# contra1579.net
KiCad netlist of a schematic drawn in EAGLE
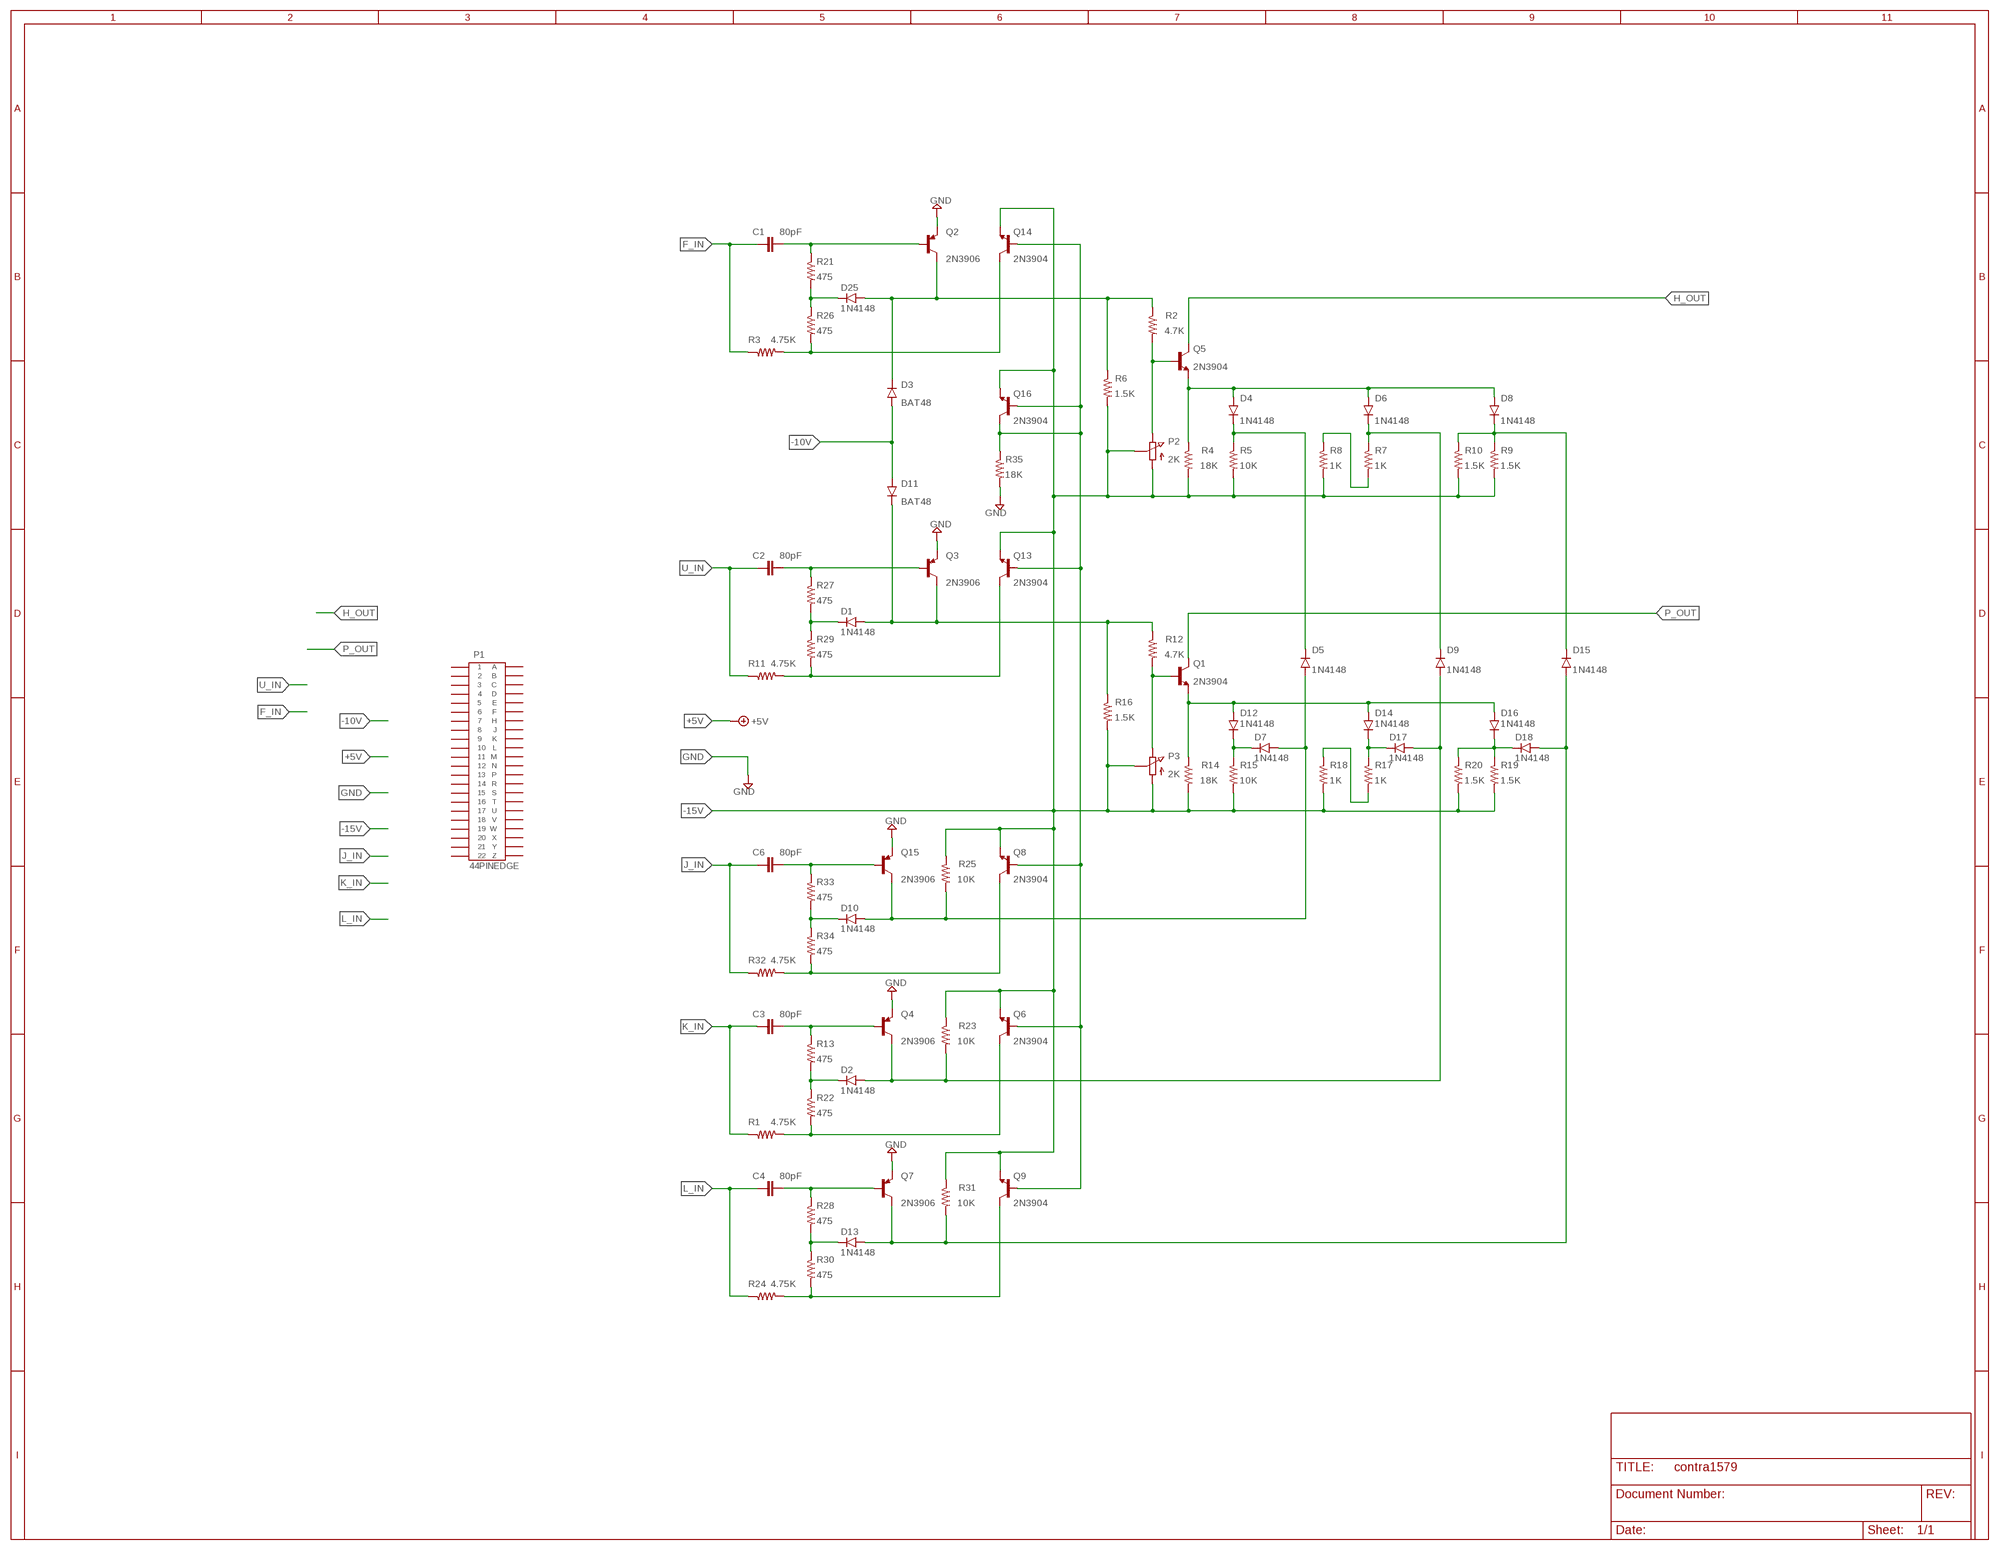
[diagram p0: schematic, sheet 1]

(export (version "E")
  (design (tool "Eeschema 10.0.6"))
  (components
    (comp (ref "C1")
      (value "80pF")
      (footprint "eagle-import:5MM_TH")
      (libsource (lib "eagle-import") (part "CAP1000PF"))
    )
    (comp (ref "C2")
      (value "80pF")
      (footprint "eagle-import:5MM_TH")
      (libsource (lib "eagle-import") (part "CAP1000PF"))
    )
    (comp (ref "C3")
      (value "80pF")
      (footprint "eagle-import:5MM_TH")
      (libsource (lib "eagle-import") (part "CAP1000PF"))
    )
    (comp (ref "C4")
      (value "80pF")
      (footprint "eagle-import:5MM_TH")
      (libsource (lib "eagle-import") (part "CAP1000PF"))
    )
    (comp (ref "C6")
      (value "80pF")
      (footprint "eagle-import:5MM_TH")
      (libsource (lib "eagle-import") (part "CAP1000PF"))
    )
    (comp (ref "D1")
      (value "1N4148")
      (footprint "eagle-import:DO35-7")
      (libsource (lib "eagle-import") (part "1N4148"))
    )
    (comp (ref "D2")
      (value "1N4148")
      (footprint "eagle-import:DO35-7")
      (libsource (lib "eagle-import") (part "1N4148"))
    )
    (comp (ref "D3")
      (value "BAT48")
      (footprint "eagle-import:DO35-7")
      (libsource (lib "eagle-import") (part "1N4148"))
    )
    (comp (ref "D4")
      (value "1N4148")
      (footprint "eagle-import:DO35-7")
      (libsource (lib "eagle-import") (part "1N4148"))
    )
    (comp (ref "D5")
      (value "1N4148")
      (footprint "eagle-import:DO35-7")
      (libsource (lib "eagle-import") (part "1N4148"))
    )
    (comp (ref "D6")
      (value "1N4148")
      (footprint "eagle-import:DO35-7")
      (libsource (lib "eagle-import") (part "1N4148"))
    )
    (comp (ref "D7")
      (value "1N4148")
      (footprint "eagle-import:DO35-7")
      (libsource (lib "eagle-import") (part "1N4148"))
    )
    (comp (ref "D8")
      (value "1N4148")
      (footprint "eagle-import:DO35-7")
      (libsource (lib "eagle-import") (part "1N4148"))
    )
    (comp (ref "D9")
      (value "1N4148")
      (footprint "eagle-import:DO35-7")
      (libsource (lib "eagle-import") (part "1N4148"))
    )
    (comp (ref "D10")
      (value "1N4148")
      (footprint "eagle-import:DO35-7")
      (libsource (lib "eagle-import") (part "1N4148"))
    )
    (comp (ref "D11")
      (value "BAT48")
      (footprint "eagle-import:DO35-7")
      (libsource (lib "eagle-import") (part "1N4148"))
    )
    (comp (ref "D12")
      (value "1N4148")
      (footprint "eagle-import:DO35-7")
      (libsource (lib "eagle-import") (part "1N4148"))
    )
    (comp (ref "D13")
      (value "1N4148")
      (footprint "eagle-import:DO35-7")
      (libsource (lib "eagle-import") (part "1N4148"))
    )
    (comp (ref "D14")
      (value "1N4148")
      (footprint "eagle-import:DO35-7")
      (libsource (lib "eagle-import") (part "1N4148"))
    )
    (comp (ref "D15")
      (value "1N4148")
      (footprint "eagle-import:DO35-7")
      (libsource (lib "eagle-import") (part "1N4148"))
    )
    (comp (ref "D16")
      (value "1N4148")
      (footprint "eagle-import:DO35-7")
      (libsource (lib "eagle-import") (part "1N4148"))
    )
    (comp (ref "D17")
      (value "1N4148")
      (footprint "eagle-import:DO35-7")
      (libsource (lib "eagle-import") (part "1N4148"))
    )
    (comp (ref "D18")
      (value "1N4148")
      (footprint "eagle-import:DO35-7")
      (libsource (lib "eagle-import") (part "1N4148"))
    )
    (comp (ref "D25")
      (value "1N4148")
      (footprint "eagle-import:DO35-7")
      (libsource (lib "eagle-import") (part "1N4148"))
    )
    (comp (ref "P1")
      (value "44PINEDGE")
      (footprint "eagle-import:44PINEDGE")
      (libsource (lib "eagle-import") (part "44PINEDGE"))
    )
    (comp (ref "P2")
      (value "2K")
      (footprint "eagle-import:3006P")
      (libsource (lib "eagle-import") (part "POT-3006P"))
    )
    (comp (ref "P3")
      (value "2K")
      (footprint "eagle-import:3006P")
      (libsource (lib "eagle-import") (part "POT-3006P"))
    )
    (comp (ref "Q1")
      (value "2N3904")
      (footprint "eagle-import:TO92")
      (libsource (lib "eagle-import") (part "2N3904"))
    )
    (comp (ref "Q2")
      (value "2N3906")
      (footprint "eagle-import:TO92")
      (libsource (lib "eagle-import") (part "2N3906"))
    )
    (comp (ref "Q3")
      (value "2N3906")
      (footprint "eagle-import:TO92")
      (libsource (lib "eagle-import") (part "2N3906"))
    )
    (comp (ref "Q4")
      (value "2N3906")
      (footprint "eagle-import:TO92")
      (libsource (lib "eagle-import") (part "2N3906"))
    )
    (comp (ref "Q5")
      (value "2N3904")
      (footprint "eagle-import:TO92")
      (libsource (lib "eagle-import") (part "2N3904"))
    )
    (comp (ref "Q6")
      (value "2N3904")
      (footprint "eagle-import:TO92")
      (libsource (lib "eagle-import") (part "2N3904"))
    )
    (comp (ref "Q7")
      (value "2N3906")
      (footprint "eagle-import:TO92")
      (libsource (lib "eagle-import") (part "2N3906"))
    )
    (comp (ref "Q8")
      (value "2N3904")
      (footprint "eagle-import:TO92")
      (libsource (lib "eagle-import") (part "2N3904"))
    )
    (comp (ref "Q9")
      (value "2N3904")
      (footprint "eagle-import:TO92")
      (libsource (lib "eagle-import") (part "2N3904"))
    )
    (comp (ref "Q13")
      (value "2N3904")
      (footprint "eagle-import:TO92")
      (libsource (lib "eagle-import") (part "2N3904"))
    )
    (comp (ref "Q14")
      (value "2N3904")
      (footprint "eagle-import:TO92")
      (libsource (lib "eagle-import") (part "2N3904"))
    )
    (comp (ref "Q15")
      (value "2N3906")
      (footprint "eagle-import:TO92")
      (libsource (lib "eagle-import") (part "2N3906"))
    )
    (comp (ref "Q16")
      (value "2N3904")
      (footprint "eagle-import:TO92")
      (libsource (lib "eagle-import") (part "2N3904"))
    )
    (comp (ref "R1")
      (value "4.75K")
      (footprint "eagle-import:0207_10")
      (libsource (lib "eagle-import") (part "R-1/4WATT"))
    )
    (comp (ref "R2")
      (value "4.7K")
      (footprint "eagle-import:0207_10")
      (libsource (lib "eagle-import") (part "R-1/4WATT"))
    )
    (comp (ref "R3")
      (value "4.75K")
      (footprint "eagle-import:0207_10")
      (libsource (lib "eagle-import") (part "R-1/4WATT"))
    )
    (comp (ref "R4")
      (value "18K")
      (footprint "eagle-import:0207_10")
      (libsource (lib "eagle-import") (part "R-1/4WATT"))
    )
    (comp (ref "R5")
      (value "10K")
      (footprint "eagle-import:0207_10")
      (libsource (lib "eagle-import") (part "R-1/4WATT"))
    )
    (comp (ref "R6")
      (value "1.5K")
      (footprint "eagle-import:0207_10")
      (libsource (lib "eagle-import") (part "R-1/4WATT"))
    )
    (comp (ref "R7")
      (value "1K")
      (footprint "eagle-import:0207_10")
      (libsource (lib "eagle-import") (part "R-1/4WATT"))
    )
    (comp (ref "R8")
      (value "1K")
      (footprint "eagle-import:0207_10")
      (libsource (lib "eagle-import") (part "R-1/4WATT"))
    )
    (comp (ref "R9")
      (value "1.5K")
      (footprint "eagle-import:0207_10")
      (libsource (lib "eagle-import") (part "R-1/4WATT"))
    )
    (comp (ref "R10")
      (value "1.5K")
      (footprint "eagle-import:0207_10")
      (libsource (lib "eagle-import") (part "R-1/4WATT"))
    )
    (comp (ref "R11")
      (value "4.75K")
      (footprint "eagle-import:0207_10")
      (libsource (lib "eagle-import") (part "R-1/4WATT"))
    )
    (comp (ref "R12")
      (value "4.7K")
      (footprint "eagle-import:0207_10")
      (libsource (lib "eagle-import") (part "R-1/4WATT"))
    )
    (comp (ref "R13")
      (value "475")
      (footprint "eagle-import:0207_10")
      (libsource (lib "eagle-import") (part "R-1/4WATT"))
    )
    (comp (ref "R14")
      (value "18K")
      (footprint "eagle-import:0207_10")
      (libsource (lib "eagle-import") (part "R-1/4WATT"))
    )
    (comp (ref "R15")
      (value "10K")
      (footprint "eagle-import:0207_10")
      (libsource (lib "eagle-import") (part "R-1/4WATT"))
    )
    (comp (ref "R16")
      (value "1.5K")
      (footprint "eagle-import:0207_10")
      (libsource (lib "eagle-import") (part "R-1/4WATT"))
    )
    (comp (ref "R17")
      (value "1K")
      (footprint "eagle-import:0207_10")
      (libsource (lib "eagle-import") (part "R-1/4WATT"))
    )
    (comp (ref "R18")
      (value "1K")
      (footprint "eagle-import:0207_10")
      (libsource (lib "eagle-import") (part "R-1/4WATT"))
    )
    (comp (ref "R19")
      (value "1.5K")
      (footprint "eagle-import:0207_10")
      (libsource (lib "eagle-import") (part "R-1/4WATT"))
    )
    (comp (ref "R20")
      (value "1.5K")
      (footprint "eagle-import:0207_10")
      (libsource (lib "eagle-import") (part "R-1/4WATT"))
    )
    (comp (ref "R21")
      (value "475")
      (footprint "eagle-import:0207_10")
      (libsource (lib "eagle-import") (part "R-1/4WATT"))
    )
    (comp (ref "R22")
      (value "475")
      (footprint "eagle-import:0207_10")
      (libsource (lib "eagle-import") (part "R-1/4WATT"))
    )
    (comp (ref "R23")
      (value "10K")
      (footprint "eagle-import:0207_10")
      (libsource (lib "eagle-import") (part "R-1/4WATT"))
    )
    (comp (ref "R24")
      (value "4.75K")
      (footprint "eagle-import:0207_10")
      (libsource (lib "eagle-import") (part "R-1/4WATT"))
    )
    (comp (ref "R25")
      (value "10K")
      (footprint "eagle-import:0207_10")
      (libsource (lib "eagle-import") (part "R-1/4WATT"))
    )
    (comp (ref "R26")
      (value "475")
      (footprint "eagle-import:0207_10")
      (libsource (lib "eagle-import") (part "R-1/4WATT"))
    )
    (comp (ref "R27")
      (value "475")
      (footprint "eagle-import:0207_10")
      (libsource (lib "eagle-import") (part "R-1/4WATT"))
    )
    (comp (ref "R28")
      (value "475")
      (footprint "eagle-import:0207_10")
      (libsource (lib "eagle-import") (part "R-1/4WATT"))
    )
    (comp (ref "R29")
      (value "475")
      (footprint "eagle-import:0207_10")
      (libsource (lib "eagle-import") (part "R-1/4WATT"))
    )
    (comp (ref "R30")
      (value "475")
      (footprint "eagle-import:0207_10")
      (libsource (lib "eagle-import") (part "R-1/4WATT"))
    )
    (comp (ref "R31")
      (value "10K")
      (footprint "eagle-import:0207_10")
      (libsource (lib "eagle-import") (part "R-1/4WATT"))
    )
    (comp (ref "R32")
      (value "4.75K")
      (footprint "eagle-import:0207_10")
      (libsource (lib "eagle-import") (part "R-1/4WATT"))
    )
    (comp (ref "R33")
      (value "475")
      (footprint "eagle-import:0207_10")
      (libsource (lib "eagle-import") (part "R-1/4WATT"))
    )
    (comp (ref "R34")
      (value "475")
      (footprint "eagle-import:0207_10")
      (libsource (lib "eagle-import") (part "R-1/4WATT"))
    )
    (comp (ref "R35")
      (value "18K")
      (footprint "eagle-import:0207_10")
      (libsource (lib "eagle-import") (part "R-1/4WATT"))
    )
  )
  (nets
    (net (code "2") (name "-10V") (class "Default")
      (node (ref "D11") (pin "A") (pinfunction "A_A") (pintype "passive"))
      (node (ref "D3") (pin "A") (pinfunction "A_A") (pintype "passive"))
    )
    (net (code "3") (name "-15V") (class "Default")
      (node (ref "P2") (pin "1") (pinfunction "A_1") (pintype "passive"))
      (node (ref "P2") (pin "2") (pinfunction "S_2") (pintype "passive"))
      (node (ref "P3") (pin "1") (pinfunction "A_1") (pintype "passive"))
      (node (ref "P3") (pin "2") (pinfunction "S_2") (pintype "passive"))
      (node (ref "Q13") (pin "3") (pinfunction "E_3") (pintype "passive"))
      (node (ref "Q14") (pin "3") (pinfunction "E_3") (pintype "passive"))
      (node (ref "Q16") (pin "3") (pinfunction "E_3") (pintype "passive"))
      (node (ref "Q6") (pin "3") (pinfunction "E_3") (pintype "passive"))
      (node (ref "Q8") (pin "3") (pinfunction "E_3") (pintype "passive"))
      (node (ref "Q9") (pin "3") (pinfunction "E_3") (pintype "passive"))
      (node (ref "R10") (pin "2") (pinfunction "P$2_2") (pintype "passive"))
      (node (ref "R14") (pin "2") (pinfunction "P$2_2") (pintype "passive"))
      (node (ref "R15") (pin "2") (pinfunction "P$2_2") (pintype "passive"))
      (node (ref "R16") (pin "2") (pinfunction "P$2_2") (pintype "passive"))
      (node (ref "R18") (pin "2") (pinfunction "P$2_2") (pintype "passive"))
      (node (ref "R19") (pin "2") (pinfunction "P$2_2") (pintype "passive"))
      (node (ref "R20") (pin "2") (pinfunction "P$2_2") (pintype "passive"))
      (node (ref "R23") (pin "1") (pinfunction "P$1_1") (pintype "passive"))
      (node (ref "R25") (pin "1") (pinfunction "P$1_1") (pintype "passive"))
      (node (ref "R31") (pin "1") (pinfunction "P$1_1") (pintype "passive"))
      (node (ref "R4") (pin "2") (pinfunction "P$2_2") (pintype "passive"))
      (node (ref "R5") (pin "2") (pinfunction "P$2_2") (pintype "passive"))
      (node (ref "R6") (pin "2") (pinfunction "P$2_2") (pintype "passive"))
      (node (ref "R8") (pin "2") (pinfunction "P$2_2") (pintype "passive"))
      (node (ref "R9") (pin "2") (pinfunction "P$2_2") (pintype "passive"))
    )
    (net (code "4") (name "F_IN") (class "Default")
      (node (ref "C1") (pin "1") (pinfunction "1_1") (pintype "passive"))
      (node (ref "R3") (pin "1") (pinfunction "P$1_1") (pintype "passive"))
    )
    (net (code "5") (name "GND") (class "Default")
      (node (ref "Q15") (pin "3") (pinfunction "E_3") (pintype "passive"))
      (node (ref "Q2") (pin "3") (pinfunction "E_3") (pintype "passive"))
      (node (ref "Q3") (pin "3") (pinfunction "E_3") (pintype "passive"))
      (node (ref "Q4") (pin "3") (pinfunction "E_3") (pintype "passive"))
      (node (ref "Q7") (pin "3") (pinfunction "E_3") (pintype "passive"))
      (node (ref "R35") (pin "2") (pinfunction "P$2_2") (pintype "passive"))
    )
    (net (code "6") (name "H_OUT") (class "Default")
      (node (ref "Q5") (pin "1") (pinfunction "C_1") (pintype "passive"))
    )
    (net (code "7") (name "J_IN") (class "Default")
      (node (ref "C6") (pin "1") (pinfunction "1_1") (pintype "passive"))
      (node (ref "R32") (pin "1") (pinfunction "P$1_1") (pintype "passive"))
    )
    (net (code "8") (name "K_IN") (class "Default")
      (node (ref "C3") (pin "1") (pinfunction "1_1") (pintype "passive"))
      (node (ref "R1") (pin "1") (pinfunction "P$1_1") (pintype "passive"))
    )
    (net (code "9") (name "L_IN") (class "Default")
      (node (ref "C4") (pin "1") (pinfunction "1_1") (pintype "passive"))
      (node (ref "R24") (pin "1") (pinfunction "P$1_1") (pintype "passive"))
    )
    (net (code "10") (name "Net-(P2-E)") (class "Default")
      (node (ref "P2") (pin "3") (pinfunction "E_3") (pintype "passive"))
      (node (ref "Q5") (pin "2") (pinfunction "B_2") (pintype "passive"))
      (node (ref "R2") (pin "2") (pinfunction "P$2_2") (pintype "passive"))
    )
    (net (code "11") (name "Net-(P3-E)") (class "Default")
      (node (ref "P3") (pin "3") (pinfunction "E_3") (pintype "passive"))
      (node (ref "Q1") (pin "2") (pinfunction "B_2") (pintype "passive"))
      (node (ref "R12") (pin "2") (pinfunction "P$2_2") (pintype "passive"))
    )
    (net (code "12") (name "Net-(Q1-E)") (class "Default")
      (node (ref "D12") (pin "A") (pinfunction "A_A") (pintype "passive"))
      (node (ref "D14") (pin "A") (pinfunction "A_A") (pintype "passive"))
      (node (ref "D16") (pin "A") (pinfunction "A_A") (pintype "passive"))
      (node (ref "Q1") (pin "3") (pinfunction "E_3") (pintype "passive"))
      (node (ref "R14") (pin "1") (pinfunction "P$1_1") (pintype "passive"))
    )
    (net (code "13") (name "Net-(Q2-B)") (class "Default")
      (node (ref "C1") (pin "2") (pinfunction "2_2") (pintype "passive"))
      (node (ref "Q2") (pin "2") (pinfunction "B_2") (pintype "passive"))
      (node (ref "R21") (pin "1") (pinfunction "P$1_1") (pintype "passive"))
    )
    (net (code "14") (name "Net-(Q2-C)") (class "Default")
      (node (ref "D25") (pin "A") (pinfunction "A_A") (pintype "passive"))
      (node (ref "D3") (pin "C") (pinfunction "C_C") (pintype "passive"))
      (node (ref "Q2") (pin "1") (pinfunction "C_1") (pintype "passive"))
      (node (ref "R2") (pin "1") (pinfunction "P$1_1") (pintype "passive"))
      (node (ref "R6") (pin "1") (pinfunction "P$1_1") (pintype "passive"))
    )
    (net (code "15") (name "Net-(Q3-B)") (class "Default")
      (node (ref "C2") (pin "2") (pinfunction "2_2") (pintype "passive"))
      (node (ref "Q3") (pin "2") (pinfunction "B_2") (pintype "passive"))
      (node (ref "R27") (pin "1") (pinfunction "P$1_1") (pintype "passive"))
    )
    (net (code "16") (name "Net-(Q3-C)") (class "Default")
      (node (ref "D1") (pin "A") (pinfunction "A_A") (pintype "passive"))
      (node (ref "D11") (pin "C") (pinfunction "C_C") (pintype "passive"))
      (node (ref "Q3") (pin "1") (pinfunction "C_1") (pintype "passive"))
      (node (ref "R12") (pin "1") (pinfunction "P$1_1") (pintype "passive"))
      (node (ref "R16") (pin "1") (pinfunction "P$1_1") (pintype "passive"))
    )
    (net (code "17") (name "Net-(Q4-B)") (class "Default")
      (node (ref "C3") (pin "2") (pinfunction "2_2") (pintype "passive"))
      (node (ref "Q4") (pin "2") (pinfunction "B_2") (pintype "passive"))
      (node (ref "R13") (pin "1") (pinfunction "P$1_1") (pintype "passive"))
    )
    (net (code "18") (name "Net-(Q4-C)") (class "Default")
      (node (ref "D17") (pin "A") (pinfunction "A_A") (pintype "passive"))
      (node (ref "D2") (pin "A") (pinfunction "A_A") (pintype "passive"))
      (node (ref "D9") (pin "A") (pinfunction "A_A") (pintype "passive"))
      (node (ref "Q4") (pin "1") (pinfunction "C_1") (pintype "passive"))
      (node (ref "R23") (pin "2") (pinfunction "P$2_2") (pintype "passive"))
    )
    (net (code "19") (name "Net-(Q5-E)") (class "Default")
      (node (ref "D4") (pin "A") (pinfunction "A_A") (pintype "passive"))
      (node (ref "D6") (pin "A") (pinfunction "A_A") (pintype "passive"))
      (node (ref "D8") (pin "A") (pinfunction "A_A") (pintype "passive"))
      (node (ref "Q5") (pin "3") (pinfunction "E_3") (pintype "passive"))
      (node (ref "R4") (pin "1") (pinfunction "P$1_1") (pintype "passive"))
    )
    (net (code "20") (name "Net-(Q6-C)") (class "Default")
      (node (ref "Q6") (pin "1") (pinfunction "C_1") (pintype "passive"))
      (node (ref "R1") (pin "2") (pinfunction "P$2_2") (pintype "passive"))
      (node (ref "R22") (pin "2") (pinfunction "P$2_2") (pintype "passive"))
    )
    (net (code "21") (name "Net-(Q7-B)") (class "Default")
      (node (ref "C4") (pin "2") (pinfunction "2_2") (pintype "passive"))
      (node (ref "Q7") (pin "2") (pinfunction "B_2") (pintype "passive"))
      (node (ref "R28") (pin "1") (pinfunction "P$1_1") (pintype "passive"))
    )
    (net (code "22") (name "Net-(Q7-C)") (class "Default")
      (node (ref "D13") (pin "A") (pinfunction "A_A") (pintype "passive"))
      (node (ref "D15") (pin "A") (pinfunction "A_A") (pintype "passive"))
      (node (ref "D18") (pin "A") (pinfunction "A_A") (pintype "passive"))
      (node (ref "Q7") (pin "1") (pinfunction "C_1") (pintype "passive"))
      (node (ref "R31") (pin "2") (pinfunction "P$2_2") (pintype "passive"))
    )
    (net (code "23") (name "Net-(Q8-C)") (class "Default")
      (node (ref "Q8") (pin "1") (pinfunction "C_1") (pintype "passive"))
      (node (ref "R32") (pin "2") (pinfunction "P$2_2") (pintype "passive"))
      (node (ref "R34") (pin "2") (pinfunction "P$2_2") (pintype "passive"))
    )
    (net (code "24") (name "Net-(Q9-C)") (class "Default")
      (node (ref "Q9") (pin "1") (pinfunction "C_1") (pintype "passive"))
      (node (ref "R24") (pin "2") (pinfunction "P$2_2") (pintype "passive"))
      (node (ref "R30") (pin "2") (pinfunction "P$2_2") (pintype "passive"))
    )
    (net (code "25") (name "Net-(Q13-B)") (class "Default")
      (node (ref "Q13") (pin "2") (pinfunction "B_2") (pintype "passive"))
      (node (ref "Q14") (pin "2") (pinfunction "B_2") (pintype "passive"))
      (node (ref "Q16") (pin "1") (pinfunction "C_1") (pintype "passive"))
      (node (ref "Q16") (pin "2") (pinfunction "B_2") (pintype "passive"))
      (node (ref "Q6") (pin "2") (pinfunction "B_2") (pintype "passive"))
      (node (ref "Q8") (pin "2") (pinfunction "B_2") (pintype "passive"))
      (node (ref "Q9") (pin "2") (pinfunction "B_2") (pintype "passive"))
      (node (ref "R35") (pin "1") (pinfunction "P$1_1") (pintype "passive"))
    )
    (net (code "26") (name "Net-(Q13-C)") (class "Default")
      (node (ref "Q13") (pin "1") (pinfunction "C_1") (pintype "passive"))
      (node (ref "R11") (pin "2") (pinfunction "P$2_2") (pintype "passive"))
      (node (ref "R29") (pin "2") (pinfunction "P$2_2") (pintype "passive"))
    )
    (net (code "27") (name "Net-(Q14-C)") (class "Default")
      (node (ref "Q14") (pin "1") (pinfunction "C_1") (pintype "passive"))
      (node (ref "R26") (pin "2") (pinfunction "P$2_2") (pintype "passive"))
      (node (ref "R3") (pin "2") (pinfunction "P$2_2") (pintype "passive"))
    )
    (net (code "28") (name "Net-(Q15-B)") (class "Default")
      (node (ref "C6") (pin "2") (pinfunction "2_2") (pintype "passive"))
      (node (ref "Q15") (pin "2") (pinfunction "B_2") (pintype "passive"))
      (node (ref "R33") (pin "1") (pinfunction "P$1_1") (pintype "passive"))
    )
    (net (code "29") (name "Net-(Q15-C)") (class "Default")
      (node (ref "D10") (pin "A") (pinfunction "A_A") (pintype "passive"))
      (node (ref "D5") (pin "A") (pinfunction "A_A") (pintype "passive"))
      (node (ref "D7") (pin "A") (pinfunction "A_A") (pintype "passive"))
      (node (ref "Q15") (pin "1") (pinfunction "C_1") (pintype "passive"))
      (node (ref "R25") (pin "2") (pinfunction "P$2_2") (pintype "passive"))
    )
    (net (code "30") (name "Net-(R5-P$1)") (class "Default")
      (node (ref "D4") (pin "C") (pinfunction "C_C") (pintype "passive"))
      (node (ref "D5") (pin "C") (pinfunction "C_C") (pintype "passive"))
      (node (ref "R5") (pin "1") (pinfunction "P$1_1") (pintype "passive"))
    )
    (net (code "31") (name "Net-(R7-P$1)") (class "Default")
      (node (ref "D6") (pin "C") (pinfunction "C_C") (pintype "passive"))
      (node (ref "D9") (pin "C") (pinfunction "C_C") (pintype "passive"))
      (node (ref "R7") (pin "1") (pinfunction "P$1_1") (pintype "passive"))
    )
    (net (code "32") (name "Net-(R7-P$2)") (class "Default")
      (node (ref "R7") (pin "2") (pinfunction "P$2_2") (pintype "passive"))
      (node (ref "R8") (pin "1") (pinfunction "P$1_1") (pintype "passive"))
    )
    (net (code "33") (name "Net-(R10-P$1)") (class "Default")
      (node (ref "D15") (pin "C") (pinfunction "C_C") (pintype "passive"))
      (node (ref "D8") (pin "C") (pinfunction "C_C") (pintype "passive"))
      (node (ref "R10") (pin "1") (pinfunction "P$1_1") (pintype "passive"))
      (node (ref "R9") (pin "1") (pinfunction "P$1_1") (pintype "passive"))
    )
    (net (code "34") (name "Net-(R13-P$2)") (class "Default")
      (node (ref "D2") (pin "C") (pinfunction "C_C") (pintype "passive"))
      (node (ref "R13") (pin "2") (pinfunction "P$2_2") (pintype "passive"))
      (node (ref "R22") (pin "1") (pinfunction "P$1_1") (pintype "passive"))
    )
    (net (code "35") (name "Net-(R15-P$1)") (class "Default")
      (node (ref "D12") (pin "C") (pinfunction "C_C") (pintype "passive"))
      (node (ref "D7") (pin "C") (pinfunction "C_C") (pintype "passive"))
      (node (ref "R15") (pin "1") (pinfunction "P$1_1") (pintype "passive"))
    )
    (net (code "36") (name "Net-(R17-P$1)") (class "Default")
      (node (ref "D14") (pin "C") (pinfunction "C_C") (pintype "passive"))
      (node (ref "D17") (pin "C") (pinfunction "C_C") (pintype "passive"))
      (node (ref "R17") (pin "1") (pinfunction "P$1_1") (pintype "passive"))
    )
    (net (code "37") (name "Net-(R17-P$2)") (class "Default")
      (node (ref "R17") (pin "2") (pinfunction "P$2_2") (pintype "passive"))
      (node (ref "R18") (pin "1") (pinfunction "P$1_1") (pintype "passive"))
    )
    (net (code "38") (name "Net-(R19-P$1)") (class "Default")
      (node (ref "D16") (pin "C") (pinfunction "C_C") (pintype "passive"))
      (node (ref "D18") (pin "C") (pinfunction "C_C") (pintype "passive"))
      (node (ref "R19") (pin "1") (pinfunction "P$1_1") (pintype "passive"))
      (node (ref "R20") (pin "1") (pinfunction "P$1_1") (pintype "passive"))
    )
    (net (code "39") (name "Net-(R21-P$2)") (class "Default")
      (node (ref "D25") (pin "C") (pinfunction "C_C") (pintype "passive"))
      (node (ref "R21") (pin "2") (pinfunction "P$2_2") (pintype "passive"))
      (node (ref "R26") (pin "1") (pinfunction "P$1_1") (pintype "passive"))
    )
    (net (code "40") (name "Net-(R27-P$2)") (class "Default")
      (node (ref "D1") (pin "C") (pinfunction "C_C") (pintype "passive"))
      (node (ref "R27") (pin "2") (pinfunction "P$2_2") (pintype "passive"))
      (node (ref "R29") (pin "1") (pinfunction "P$1_1") (pintype "passive"))
    )
    (net (code "41") (name "Net-(R28-P$2)") (class "Default")
      (node (ref "D13") (pin "C") (pinfunction "C_C") (pintype "passive"))
      (node (ref "R28") (pin "2") (pinfunction "P$2_2") (pintype "passive"))
      (node (ref "R30") (pin "1") (pinfunction "P$1_1") (pintype "passive"))
    )
    (net (code "42") (name "Net-(R33-P$2)") (class "Default")
      (node (ref "D10") (pin "C") (pinfunction "C_C") (pintype "passive"))
      (node (ref "R33") (pin "2") (pinfunction "P$2_2") (pintype "passive"))
      (node (ref "R34") (pin "1") (pinfunction "P$1_1") (pintype "passive"))
    )
    (net (code "43") (name "P_OUT") (class "Default")
      (node (ref "Q1") (pin "1") (pinfunction "C_1") (pintype "passive"))
    )
    (net (code "44") (name "U_IN") (class "Default")
      (node (ref "C2") (pin "1") (pinfunction "1_1") (pintype "passive"))
      (node (ref "R11") (pin "1") (pinfunction "P$1_1") (pintype "passive"))
    )
    (net (code "45") (name "unconnected-(P1-Pad1)") (class "Default")
      (node (ref "P1") (pin "1") (pinfunction "1_1") (pintype "passive"))
    )
    (net (code "46") (name "unconnected-(P1-Pad2)") (class "Default")
      (node (ref "P1") (pin "2") (pinfunction "2_2") (pintype "passive"))
    )
    (net (code "47") (name "unconnected-(P1-Pad3)") (class "Default")
      (node (ref "P1") (pin "3") (pinfunction "3_3") (pintype "passive"))
    )
    (net (code "48") (name "unconnected-(P1-Pad4)") (class "Default")
      (node (ref "P1") (pin "4") (pinfunction "4_4") (pintype "passive"))
    )
    (net (code "49") (name "unconnected-(P1-Pad5)") (class "Default")
      (node (ref "P1") (pin "5") (pinfunction "5_5") (pintype "passive"))
    )
    (net (code "50") (name "unconnected-(P1-Pad6)") (class "Default")
      (node (ref "P1") (pin "6") (pinfunction "6_6") (pintype "passive"))
    )
    (net (code "51") (name "unconnected-(P1-Pad7)") (class "Default")
      (node (ref "P1") (pin "7") (pinfunction "7_7") (pintype "passive"))
    )
    (net (code "52") (name "unconnected-(P1-Pad8)") (class "Default")
      (node (ref "P1") (pin "8") (pinfunction "8_8") (pintype "passive"))
    )
    (net (code "53") (name "unconnected-(P1-Pad9)") (class "Default")
      (node (ref "P1") (pin "9") (pinfunction "9_9") (pintype "passive"))
    )
    (net (code "54") (name "unconnected-(P1-Pad10)") (class "Default")
      (node (ref "P1") (pin "10") (pinfunction "10_10") (pintype "passive"))
    )
    (net (code "55") (name "unconnected-(P1-Pad11)") (class "Default")
      (node (ref "P1") (pin "11") (pinfunction "11_11") (pintype "passive"))
    )
    (net (code "56") (name "unconnected-(P1-Pad12)") (class "Default")
      (node (ref "P1") (pin "12") (pinfunction "12_12") (pintype "passive"))
    )
    (net (code "57") (name "unconnected-(P1-Pad13)") (class "Default")
      (node (ref "P1") (pin "13") (pinfunction "13_13") (pintype "passive"))
    )
    (net (code "58") (name "unconnected-(P1-Pad14)") (class "Default")
      (node (ref "P1") (pin "14") (pinfunction "14_14") (pintype "passive"))
    )
    (net (code "59") (name "unconnected-(P1-Pad15)") (class "Default")
      (node (ref "P1") (pin "15") (pinfunction "15_15") (pintype "passive"))
    )
    (net (code "60") (name "unconnected-(P1-Pad16)") (class "Default")
      (node (ref "P1") (pin "16") (pinfunction "16_16") (pintype "passive"))
    )
    (net (code "61") (name "unconnected-(P1-Pad17)") (class "Default")
      (node (ref "P1") (pin "17") (pinfunction "17_17") (pintype "passive"))
    )
    (net (code "62") (name "unconnected-(P1-Pad18)") (class "Default")
      (node (ref "P1") (pin "18") (pinfunction "18_18") (pintype "passive"))
    )
    (net (code "63") (name "unconnected-(P1-Pad19)") (class "Default")
      (node (ref "P1") (pin "19") (pinfunction "19_19") (pintype "passive"))
    )
    (net (code "64") (name "unconnected-(P1-Pad20)") (class "Default")
      (node (ref "P1") (pin "20") (pinfunction "20_20") (pintype "passive"))
    )
    (net (code "65") (name "unconnected-(P1-Pad21)") (class "Default")
      (node (ref "P1") (pin "21") (pinfunction "21_21") (pintype "passive"))
    )
    (net (code "66") (name "unconnected-(P1-Pad22)") (class "Default")
      (node (ref "P1") (pin "22") (pinfunction "22_22") (pintype "passive"))
    )
    (net (code "67") (name "unconnected-(P1-PadA)") (class "Default")
      (node (ref "P1") (pin "A") (pinfunction "A_A") (pintype "passive"))
    )
    (net (code "68") (name "unconnected-(P1-PadB)") (class "Default")
      (node (ref "P1") (pin "B") (pinfunction "B_B") (pintype "passive"))
    )
    (net (code "69") (name "unconnected-(P1-PadC)") (class "Default")
      (node (ref "P1") (pin "C") (pinfunction "C_C") (pintype "passive"))
    )
    (net (code "70") (name "unconnected-(P1-PadD)") (class "Default")
      (node (ref "P1") (pin "D") (pinfunction "D_D") (pintype "passive"))
    )
    (net (code "71") (name "unconnected-(P1-PadE)") (class "Default")
      (node (ref "P1") (pin "E") (pinfunction "E_E") (pintype "passive"))
    )
    (net (code "72") (name "unconnected-(P1-PadF)") (class "Default")
      (node (ref "P1") (pin "F") (pinfunction "F_F") (pintype "passive"))
    )
    (net (code "73") (name "unconnected-(P1-PadH)") (class "Default")
      (node (ref "P1") (pin "H") (pinfunction "H_H") (pintype "passive"))
    )
    (net (code "74") (name "unconnected-(P1-PadJ)") (class "Default")
      (node (ref "P1") (pin "J") (pinfunction "J_J") (pintype "passive"))
    )
    (net (code "75") (name "unconnected-(P1-PadK)") (class "Default")
      (node (ref "P1") (pin "K") (pinfunction "K_K") (pintype "passive"))
    )
    (net (code "76") (name "unconnected-(P1-PadL)") (class "Default")
      (node (ref "P1") (pin "L") (pinfunction "L_L") (pintype "passive"))
    )
    (net (code "77") (name "unconnected-(P1-PadM)") (class "Default")
      (node (ref "P1") (pin "M") (pinfunction "M_M") (pintype "passive"))
    )
    (net (code "78") (name "unconnected-(P1-PadN)") (class "Default")
      (node (ref "P1") (pin "N") (pinfunction "N_N") (pintype "passive"))
    )
    (net (code "79") (name "unconnected-(P1-PadP)") (class "Default")
      (node (ref "P1") (pin "P") (pinfunction "P_P") (pintype "passive"))
    )
    (net (code "80") (name "unconnected-(P1-PadR)") (class "Default")
      (node (ref "P1") (pin "R") (pinfunction "R_R") (pintype "passive"))
    )
    (net (code "81") (name "unconnected-(P1-PadS)") (class "Default")
      (node (ref "P1") (pin "S") (pinfunction "S_S") (pintype "passive"))
    )
    (net (code "82") (name "unconnected-(P1-PadT)") (class "Default")
      (node (ref "P1") (pin "T") (pinfunction "T_T") (pintype "passive"))
    )
    (net (code "83") (name "unconnected-(P1-PadU)") (class "Default")
      (node (ref "P1") (pin "U") (pinfunction "U_U") (pintype "passive"))
    )
    (net (code "84") (name "unconnected-(P1-PadV)") (class "Default")
      (node (ref "P1") (pin "V") (pinfunction "V_V") (pintype "passive"))
    )
    (net (code "85") (name "unconnected-(P1-PadW)") (class "Default")
      (node (ref "P1") (pin "W") (pinfunction "W_W") (pintype "passive"))
    )
    (net (code "86") (name "unconnected-(P1-PadX)") (class "Default")
      (node (ref "P1") (pin "X") (pinfunction "X_X") (pintype "passive"))
    )
    (net (code "87") (name "unconnected-(P1-PadY)") (class "Default")
      (node (ref "P1") (pin "Y") (pinfunction "Y_Y") (pintype "passive"))
    )
    (net (code "88") (name "unconnected-(P1-PadZ)") (class "Default")
      (node (ref "P1") (pin "Z") (pinfunction "Z_Z") (pintype "passive"))
    )
  )
)
